# Tau-BOTTOM.net
KiCad netlist of a schematic drawn in EAGLE
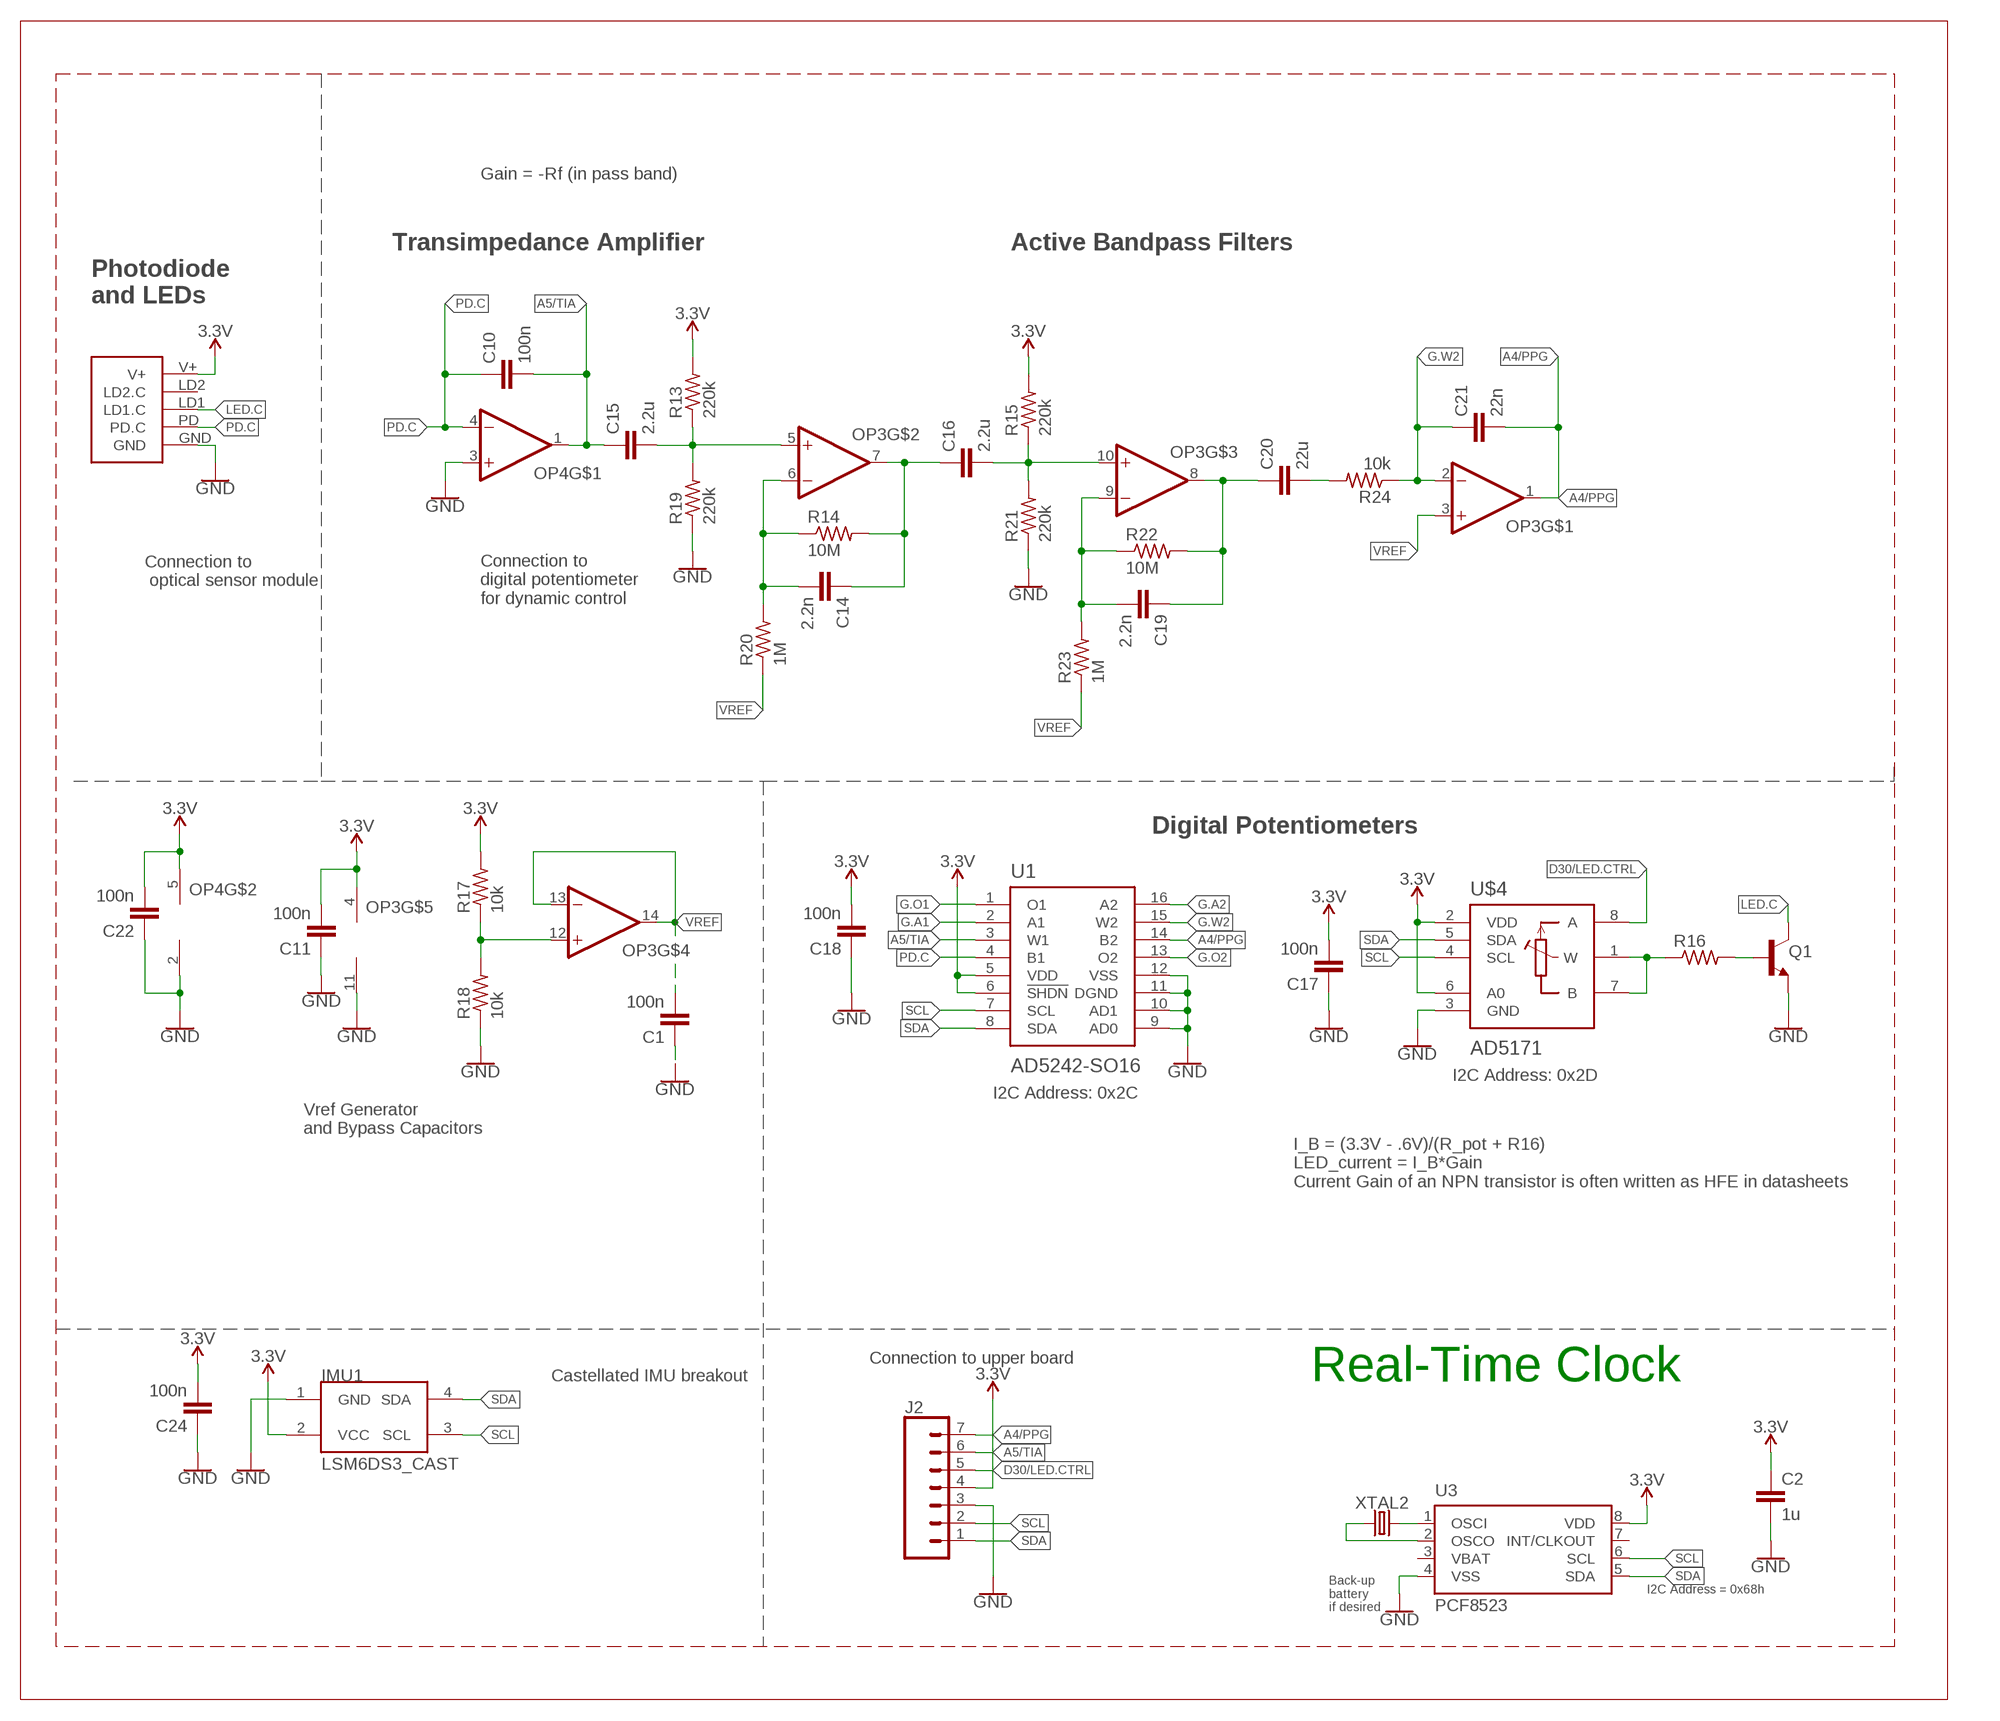
[diagram p0: schematic, sheet 1]

(export (version "E")
  (design (tool "Eeschema 10.0.6"))
  (components
    (comp (ref "C1")
      (value "100n")
      (footprint "eagle-import:C0603")
      (libsource (lib "eagle-import") (part "CAPACITOR0603"))
    )
    (comp (ref "C2")
      (value "1u")
      (footprint "eagle-import:C0603")
      (libsource (lib "eagle-import") (part "CAPACITOR0603"))
    )
    (comp (ref "C10")
      (value "100n")
      (footprint "eagle-import:C0603")
      (libsource (lib "eagle-import") (part "CAPACITOR0603"))
    )
    (comp (ref "C11")
      (value "100n")
      (footprint "eagle-import:C0603")
      (libsource (lib "eagle-import") (part "CAPACITOR0603"))
    )
    (comp (ref "C14")
      (value "2.2n")
      (footprint "eagle-import:C0603")
      (libsource (lib "eagle-import") (part "CAPACITOR0603"))
    )
    (comp (ref "C15")
      (value "2.2u")
      (footprint "eagle-import:C0603")
      (libsource (lib "eagle-import") (part "CAPACITOR0603"))
    )
    (comp (ref "C16")
      (value "2.2u")
      (footprint "eagle-import:C0603")
      (libsource (lib "eagle-import") (part "CAPACITOR0603"))
    )
    (comp (ref "C17")
      (value "100n")
      (footprint "eagle-import:C0603")
      (libsource (lib "eagle-import") (part "CAPACITOR0603"))
    )
    (comp (ref "C18")
      (value "100n")
      (footprint "eagle-import:C0603")
      (libsource (lib "eagle-import") (part "CAPACITOR0603"))
    )
    (comp (ref "C19")
      (value "2.2n")
      (footprint "eagle-import:C0603")
      (libsource (lib "eagle-import") (part "CAPACITOR0603"))
    )
    (comp (ref "C20")
      (value "22u")
      (footprint "eagle-import:C0603")
      (libsource (lib "eagle-import") (part "CAPACITOR0603"))
    )
    (comp (ref "C21")
      (value "22n")
      (footprint "eagle-import:C0603")
      (libsource (lib "eagle-import") (part "CAPACITOR0603"))
    )
    (comp (ref "C22")
      (value "100n")
      (footprint "eagle-import:C0603")
      (libsource (lib "eagle-import") (part "CAPACITOR0603"))
    )
    (comp (ref "C24")
      (value "100n")
      (footprint "eagle-import:C0603")
      (libsource (lib "eagle-import") (part "CAPACITOR0603"))
    )
    (comp (ref "IMU1")
      (value "LSM6DS3_CAST")
      (footprint "eagle-import:LSM6DS3_CAST")
      (libsource (lib "eagle-import") (part "LSM6DS3_CAST"))
    )
    (comp (ref "J2")
      (value "CONN_07-1.27MM")
      (footprint "eagle-import:1X07_1.27MM")
      (libsource (lib "eagle-import") (part "CONN_07-1.27MM"))
    )
    (comp (ref "OP3")
      (value "OP-QUAD-SO14")
      (footprint "eagle-import:SO14")
      (libsource (lib "eagle-import") (part "OP-QUAD-SO14"))
    )
    (comp (ref "OP4")
      (value "OP-SINGLEOT")
      (footprint "eagle-import:SOT23-5")
      (libsource (lib "eagle-import") (part "OP-SINGLEOT"))
    )
    (comp (ref "Q1")
      (value "NPN-GENERIC")
      (footprint "eagle-import:SOT23-3")
      (libsource (lib "eagle-import") (part "NPN-GENERIC"))
    )
    (comp (ref "R13")
      (value "220k")
      (footprint "eagle-import:R0603")
      (libsource (lib "eagle-import") (part "RESISTOR0603"))
    )
    (comp (ref "R14")
      (value "10M")
      (footprint "eagle-import:R0603")
      (libsource (lib "eagle-import") (part "RESISTOR0603"))
    )
    (comp (ref "R15")
      (value "220k")
      (footprint "eagle-import:R0603")
      (libsource (lib "eagle-import") (part "RESISTOR0603"))
    )
    (comp (ref "R16")
      (value "RESISTOR0603")
      (footprint "eagle-import:R0603")
      (libsource (lib "eagle-import") (part "RESISTOR0603"))
    )
    (comp (ref "R17")
      (value "10k")
      (footprint "eagle-import:R0402")
      (libsource (lib "eagle-import") (part "RESISTOR0402"))
    )
    (comp (ref "R18")
      (value "10k")
      (footprint "eagle-import:R0402")
      (libsource (lib "eagle-import") (part "RESISTOR0402"))
    )
    (comp (ref "R19")
      (value "220k")
      (footprint "eagle-import:R0603")
      (libsource (lib "eagle-import") (part "RESISTOR0603"))
    )
    (comp (ref "R20")
      (value "1M")
      (footprint "eagle-import:R0603")
      (libsource (lib "eagle-import") (part "RESISTOR0603"))
    )
    (comp (ref "R21")
      (value "220k")
      (footprint "eagle-import:R0603")
      (libsource (lib "eagle-import") (part "RESISTOR0603"))
    )
    (comp (ref "R22")
      (value "10M")
      (footprint "eagle-import:R0603")
      (libsource (lib "eagle-import") (part "RESISTOR0603"))
    )
    (comp (ref "R23")
      (value "1M")
      (footprint "eagle-import:R0603")
      (libsource (lib "eagle-import") (part "RESISTOR0603"))
    )
    (comp (ref "R24")
      (value "10k")
      (footprint "eagle-import:R0603")
      (libsource (lib "eagle-import") (part "RESISTOR0603"))
    )
    (comp (ref "U$3")
      (value "PPG.MODULE.2")
      (footprint "eagle-import:PPG.MODULE.2")
      (libsource (lib "eagle-import") (part "PPG.MODULE.2"))
    )
    (comp (ref "U$4")
      (value "AD5171")
      (footprint "eagle-import:SOT-23-8")
      (libsource (lib "eagle-import") (part "AD5171"))
    )
    (comp (ref "U1")
      (value "AD5242-SO16")
      (footprint "eagle-import:SO16")
      (libsource (lib "eagle-import") (part "AD5242-SO16"))
    )
    (comp (ref "U3")
      (value "PCF8523")
      (footprint "eagle-import:SO8")
      (libsource (lib "eagle-import") (part "PCF8523"))
    )
    (comp (ref "XTAL2")
      (value "32.7680kHz")
      (footprint "eagle-import:2-SMD.NOLEAD.2.0MMTO1.2MM")
      (libsource (lib "eagle-import") (part "CRYSTALECS-.327-12.5-12-C-TR"))
    )
  )
  (nets
    (net (code "1") (name "/VBAT") (class "Default")
      (node (ref "U3") (pin "3") (pinfunction "VBAT_3") (pintype "power_in"))
    )
    (net (code "2") (name "3.3V") (class "Default")
      (node (ref "C11") (pin "2") (pinfunction "2_2") (pintype "passive"))
      (node (ref "C17") (pin "2") (pinfunction "2_2") (pintype "passive"))
      (node (ref "C18") (pin "2") (pinfunction "2_2") (pintype "passive"))
      (node (ref "C2") (pin "1") (pinfunction "1_1") (pintype "passive"))
      (node (ref "C22") (pin "2") (pinfunction "2_2") (pintype "passive"))
      (node (ref "C24") (pin "2") (pinfunction "2_2") (pintype "passive"))
      (node (ref "IMU1") (pin "2") (pinfunction "VCC_2") (pintype "bidirectional"))
      (node (ref "J2") (pin "4") (pinfunction "4_4") (pintype "passive"))
      (node (ref "OP3") (pin "4") (pinfunction "V+_4") (pintype "power_in"))
      (node (ref "OP4") (pin "5") (pinfunction "V+_5") (pintype "power_in"))
      (node (ref "R13") (pin "2") (pinfunction "2_2") (pintype "passive"))
      (node (ref "R15") (pin "2") (pinfunction "2_2") (pintype "passive"))
      (node (ref "R17") (pin "2") (pinfunction "2_2") (pintype "passive"))
      (node (ref "U$3") (pin "V+") (pinfunction "V+_V+") (pintype "bidirectional"))
      (node (ref "U$4") (pin "2") (pinfunction "VDD_2") (pintype "bidirectional"))
      (node (ref "U$4") (pin "6") (pinfunction "A0_6") (pintype "bidirectional"))
      (node (ref "U1") (pin "5") (pinfunction "VDD_5") (pintype "bidirectional"))
      (node (ref "U1") (pin "6") (pinfunction "~{SHDN}_6") (pintype "bidirectional"))
      (node (ref "U3") (pin "8") (pinfunction "VDD_8") (pintype "power_in"))
    )
    (net (code "3") (name "A4{slash}PPG") (class "Default")
      (node (ref "C21") (pin "2") (pinfunction "2_2") (pintype "passive"))
      (node (ref "J2") (pin "7") (pinfunction "7_7") (pintype "passive"))
      (node (ref "OP3") (pin "1") (pinfunction "OUT_1") (pintype "output"))
      (node (ref "U1") (pin "14") (pinfunction "B2_14") (pintype "bidirectional"))
    )
    (net (code "4") (name "A5{slash}TIA") (class "Default")
      (node (ref "C10") (pin "2") (pinfunction "2_2") (pintype "passive"))
      (node (ref "C15") (pin "1") (pinfunction "1_1") (pintype "passive"))
      (node (ref "J2") (pin "6") (pinfunction "6_6") (pintype "passive"))
      (node (ref "OP4") (pin "1") (pinfunction "OUT_1") (pintype "output"))
      (node (ref "U1") (pin "3") (pinfunction "W1_3") (pintype "bidirectional"))
    )
    (net (code "5") (name "D30{slash}LED.CTRL") (class "Default")
      (node (ref "J2") (pin "5") (pinfunction "5_5") (pintype "passive"))
      (node (ref "U$4") (pin "8") (pinfunction "A_8") (pintype "bidirectional"))
    )
    (net (code "6") (name "G.A1") (class "Default")
      (node (ref "U1") (pin "2") (pinfunction "A1_2") (pintype "bidirectional"))
    )
    (net (code "7") (name "G.A2") (class "Default")
      (node (ref "U1") (pin "16") (pinfunction "A2_16") (pintype "bidirectional"))
    )
    (net (code "8") (name "G.O1") (class "Default")
      (node (ref "U1") (pin "1") (pinfunction "O1_1") (pintype "bidirectional"))
    )
    (net (code "9") (name "G.O2") (class "Default")
      (node (ref "U1") (pin "13") (pinfunction "O2_13") (pintype "bidirectional"))
    )
    (net (code "10") (name "G.W2") (class "Default")
      (node (ref "C21") (pin "1") (pinfunction "1_1") (pintype "passive"))
      (node (ref "OP3") (pin "2") (pinfunction "-IN_2") (pintype "input"))
      (node (ref "R24") (pin "1") (pinfunction "1_1") (pintype "passive"))
      (node (ref "U1") (pin "15") (pinfunction "W2_15") (pintype "bidirectional"))
    )
    (net (code "11") (name "GND") (class "Default")
      (node (ref "C1") (pin "1") (pinfunction "1_1") (pintype "passive"))
      (node (ref "C11") (pin "1") (pinfunction "1_1") (pintype "passive"))
      (node (ref "C17") (pin "1") (pinfunction "1_1") (pintype "passive"))
      (node (ref "C18") (pin "1") (pinfunction "1_1") (pintype "passive"))
      (node (ref "C2") (pin "2") (pinfunction "2_2") (pintype "passive"))
      (node (ref "C22") (pin "1") (pinfunction "1_1") (pintype "passive"))
      (node (ref "C24") (pin "1") (pinfunction "1_1") (pintype "passive"))
      (node (ref "IMU1") (pin "1") (pinfunction "GND_1") (pintype "bidirectional"))
      (node (ref "J2") (pin "3") (pinfunction "3_3") (pintype "passive"))
      (node (ref "OP3") (pin "11") (pinfunction "V-_11") (pintype "power_in"))
      (node (ref "OP4") (pin "2") (pinfunction "V-_2") (pintype "power_in"))
      (node (ref "OP4") (pin "3") (pinfunction "+IN_3") (pintype "input"))
      (node (ref "Q1") (pin "2") (pinfunction "E_2") (pintype "passive"))
      (node (ref "R18") (pin "1") (pinfunction "1_1") (pintype "passive"))
      (node (ref "R19") (pin "1") (pinfunction "1_1") (pintype "passive"))
      (node (ref "R21") (pin "1") (pinfunction "1_1") (pintype "passive"))
      (node (ref "U$3") (pin "GND") (pinfunction "GND_GND") (pintype "bidirectional"))
      (node (ref "U$4") (pin "3") (pinfunction "GND_3") (pintype "bidirectional"))
      (node (ref "U1") (pin "10") (pinfunction "AD1_10") (pintype "bidirectional"))
      (node (ref "U1") (pin "11") (pinfunction "DGND_11") (pintype "bidirectional"))
      (node (ref "U1") (pin "12") (pinfunction "VSS_12") (pintype "bidirectional"))
      (node (ref "U1") (pin "9") (pinfunction "AD0_9") (pintype "bidirectional"))
      (node (ref "U3") (pin "4") (pinfunction "VSS_4") (pintype "power_in"))
    )
    (net (code "12") (name "LED.C") (class "Default")
      (node (ref "Q1") (pin "3") (pinfunction "C_3") (pintype "passive"))
      (node (ref "U$3") (pin "LD1") (pinfunction "LD1.C_LD1") (pintype "bidirectional"))
    )
    (net (code "13") (name "Net-(C20-Pad2)") (class "Default")
      (node (ref "C20") (pin "2") (pinfunction "2_2") (pintype "passive"))
      (node (ref "R24") (pin "2") (pinfunction "2_2") (pintype "passive"))
    )
    (net (code "14") (name "Net-(OP3B-+IN)") (class "Default")
      (node (ref "C15") (pin "2") (pinfunction "2_2") (pintype "passive"))
      (node (ref "OP3") (pin "5") (pinfunction "+IN_5") (pintype "input"))
      (node (ref "R13") (pin "1") (pinfunction "1_1") (pintype "passive"))
      (node (ref "R19") (pin "2") (pinfunction "2_2") (pintype "passive"))
    )
    (net (code "15") (name "Net-(OP3B--IN)") (class "Default")
      (node (ref "C14") (pin "2") (pinfunction "2_2") (pintype "passive"))
      (node (ref "OP3") (pin "6") (pinfunction "-IN_6") (pintype "input"))
      (node (ref "R14") (pin "1") (pinfunction "1_1") (pintype "passive"))
      (node (ref "R20") (pin "2") (pinfunction "2_2") (pintype "passive"))
    )
    (net (code "16") (name "Net-(OP3B-OUT)") (class "Default")
      (node (ref "C14") (pin "1") (pinfunction "1_1") (pintype "passive"))
      (node (ref "C16") (pin "1") (pinfunction "1_1") (pintype "passive"))
      (node (ref "OP3") (pin "7") (pinfunction "OUT_7") (pintype "output"))
      (node (ref "R14") (pin "2") (pinfunction "2_2") (pintype "passive"))
    )
    (net (code "17") (name "Net-(OP3C-+IN)") (class "Default")
      (node (ref "C16") (pin "2") (pinfunction "2_2") (pintype "passive"))
      (node (ref "OP3") (pin "10") (pinfunction "+IN_10") (pintype "input"))
      (node (ref "R15") (pin "1") (pinfunction "1_1") (pintype "passive"))
      (node (ref "R21") (pin "2") (pinfunction "2_2") (pintype "passive"))
    )
    (net (code "18") (name "Net-(OP3C--IN)") (class "Default")
      (node (ref "C19") (pin "2") (pinfunction "2_2") (pintype "passive"))
      (node (ref "OP3") (pin "9") (pinfunction "-IN_9") (pintype "input"))
      (node (ref "R22") (pin "1") (pinfunction "1_1") (pintype "passive"))
      (node (ref "R23") (pin "2") (pinfunction "2_2") (pintype "passive"))
    )
    (net (code "19") (name "Net-(OP3C-OUT)") (class "Default")
      (node (ref "C19") (pin "1") (pinfunction "1_1") (pintype "passive"))
      (node (ref "C20") (pin "1") (pinfunction "1_1") (pintype "passive"))
      (node (ref "OP3") (pin "8") (pinfunction "OUT_8") (pintype "output"))
      (node (ref "R22") (pin "2") (pinfunction "2_2") (pintype "passive"))
    )
    (net (code "20") (name "Net-(OP3D-+IN)") (class "Default")
      (node (ref "OP3") (pin "12") (pinfunction "+IN_12") (pintype "input"))
      (node (ref "R17") (pin "1") (pinfunction "1_1") (pintype "passive"))
      (node (ref "R18") (pin "2") (pinfunction "2_2") (pintype "passive"))
    )
    (net (code "21") (name "Net-(Q1-B)") (class "Default")
      (node (ref "Q1") (pin "1") (pinfunction "B_1") (pintype "passive"))
      (node (ref "R16") (pin "2") (pinfunction "2_2") (pintype "passive"))
    )
    (net (code "22") (name "Net-(U$4-B)") (class "Default")
      (node (ref "R16") (pin "1") (pinfunction "1_1") (pintype "passive"))
      (node (ref "U$4") (pin "1") (pinfunction "W_1") (pintype "bidirectional"))
      (node (ref "U$4") (pin "7") (pinfunction "B_7") (pintype "bidirectional"))
    )
    (net (code "23") (name "Net-(U3-OSCI)") (class "Default")
      (node (ref "U3") (pin "1") (pinfunction "OSCI_1") (pintype "bidirectional"))
      (node (ref "XTAL2") (pin "P$2") (pinfunction "2_P$2") (pintype "passive"))
    )
    (net (code "24") (name "Net-(U3-OSCO)") (class "Default")
      (node (ref "U3") (pin "2") (pinfunction "OSCO_2") (pintype "bidirectional"))
      (node (ref "XTAL2") (pin "P$1") (pinfunction "1_P$1") (pintype "passive"))
    )
    (net (code "25") (name "PD.C") (class "Default")
      (node (ref "C10") (pin "1") (pinfunction "1_1") (pintype "passive"))
      (node (ref "OP4") (pin "4") (pinfunction "-IN_4") (pintype "input"))
      (node (ref "U$3") (pin "PD") (pinfunction "PD.C_PD") (pintype "bidirectional"))
      (node (ref "U1") (pin "4") (pinfunction "B1_4") (pintype "bidirectional"))
    )
    (net (code "26") (name "SCL") (class "Default")
      (node (ref "IMU1") (pin "3") (pinfunction "SCL_3") (pintype "bidirectional"))
      (node (ref "J2") (pin "2") (pinfunction "2_2") (pintype "passive"))
      (node (ref "U$4") (pin "4") (pinfunction "SCL_4") (pintype "bidirectional"))
      (node (ref "U1") (pin "7") (pinfunction "SCL_7") (pintype "bidirectional"))
      (node (ref "U3") (pin "6") (pinfunction "SCL_6") (pintype "bidirectional"))
    )
    (net (code "27") (name "SDA") (class "Default")
      (node (ref "IMU1") (pin "4") (pinfunction "SDA_4") (pintype "bidirectional"))
      (node (ref "J2") (pin "1") (pinfunction "1_1") (pintype "passive"))
      (node (ref "U$4") (pin "5") (pinfunction "SDA_5") (pintype "bidirectional"))
      (node (ref "U1") (pin "8") (pinfunction "SDA_8") (pintype "bidirectional"))
      (node (ref "U3") (pin "5") (pinfunction "SDA_5") (pintype "bidirectional"))
    )
    (net (code "28") (name "VREF") (class "Default")
      (node (ref "C1") (pin "2") (pinfunction "2_2") (pintype "passive"))
      (node (ref "OP3") (pin "13") (pinfunction "-IN_13") (pintype "input"))
      (node (ref "OP3") (pin "14") (pinfunction "OUT_14") (pintype "output"))
      (node (ref "OP3") (pin "3") (pinfunction "+IN_3") (pintype "input"))
      (node (ref "R20") (pin "1") (pinfunction "1_1") (pintype "passive"))
      (node (ref "R23") (pin "1") (pinfunction "1_1") (pintype "passive"))
    )
    (net (code "29") (name "unconnected-(U$3-LD2.C-PadLD2)") (class "Default")
      (node (ref "U$3") (pin "LD2") (pinfunction "LD2.C_LD2") (pintype "bidirectional"))
    )
    (net (code "30") (name "unconnected-(U3-INT{slash}CLKOUT-Pad7)") (class "Default")
      (node (ref "U3") (pin "7") (pinfunction "INT/CLKOUT_7") (pintype "bidirectional"))
    )
  )
)
